# Sheet4.net
KiCad netlist of a schematic drawn in Altium Designer
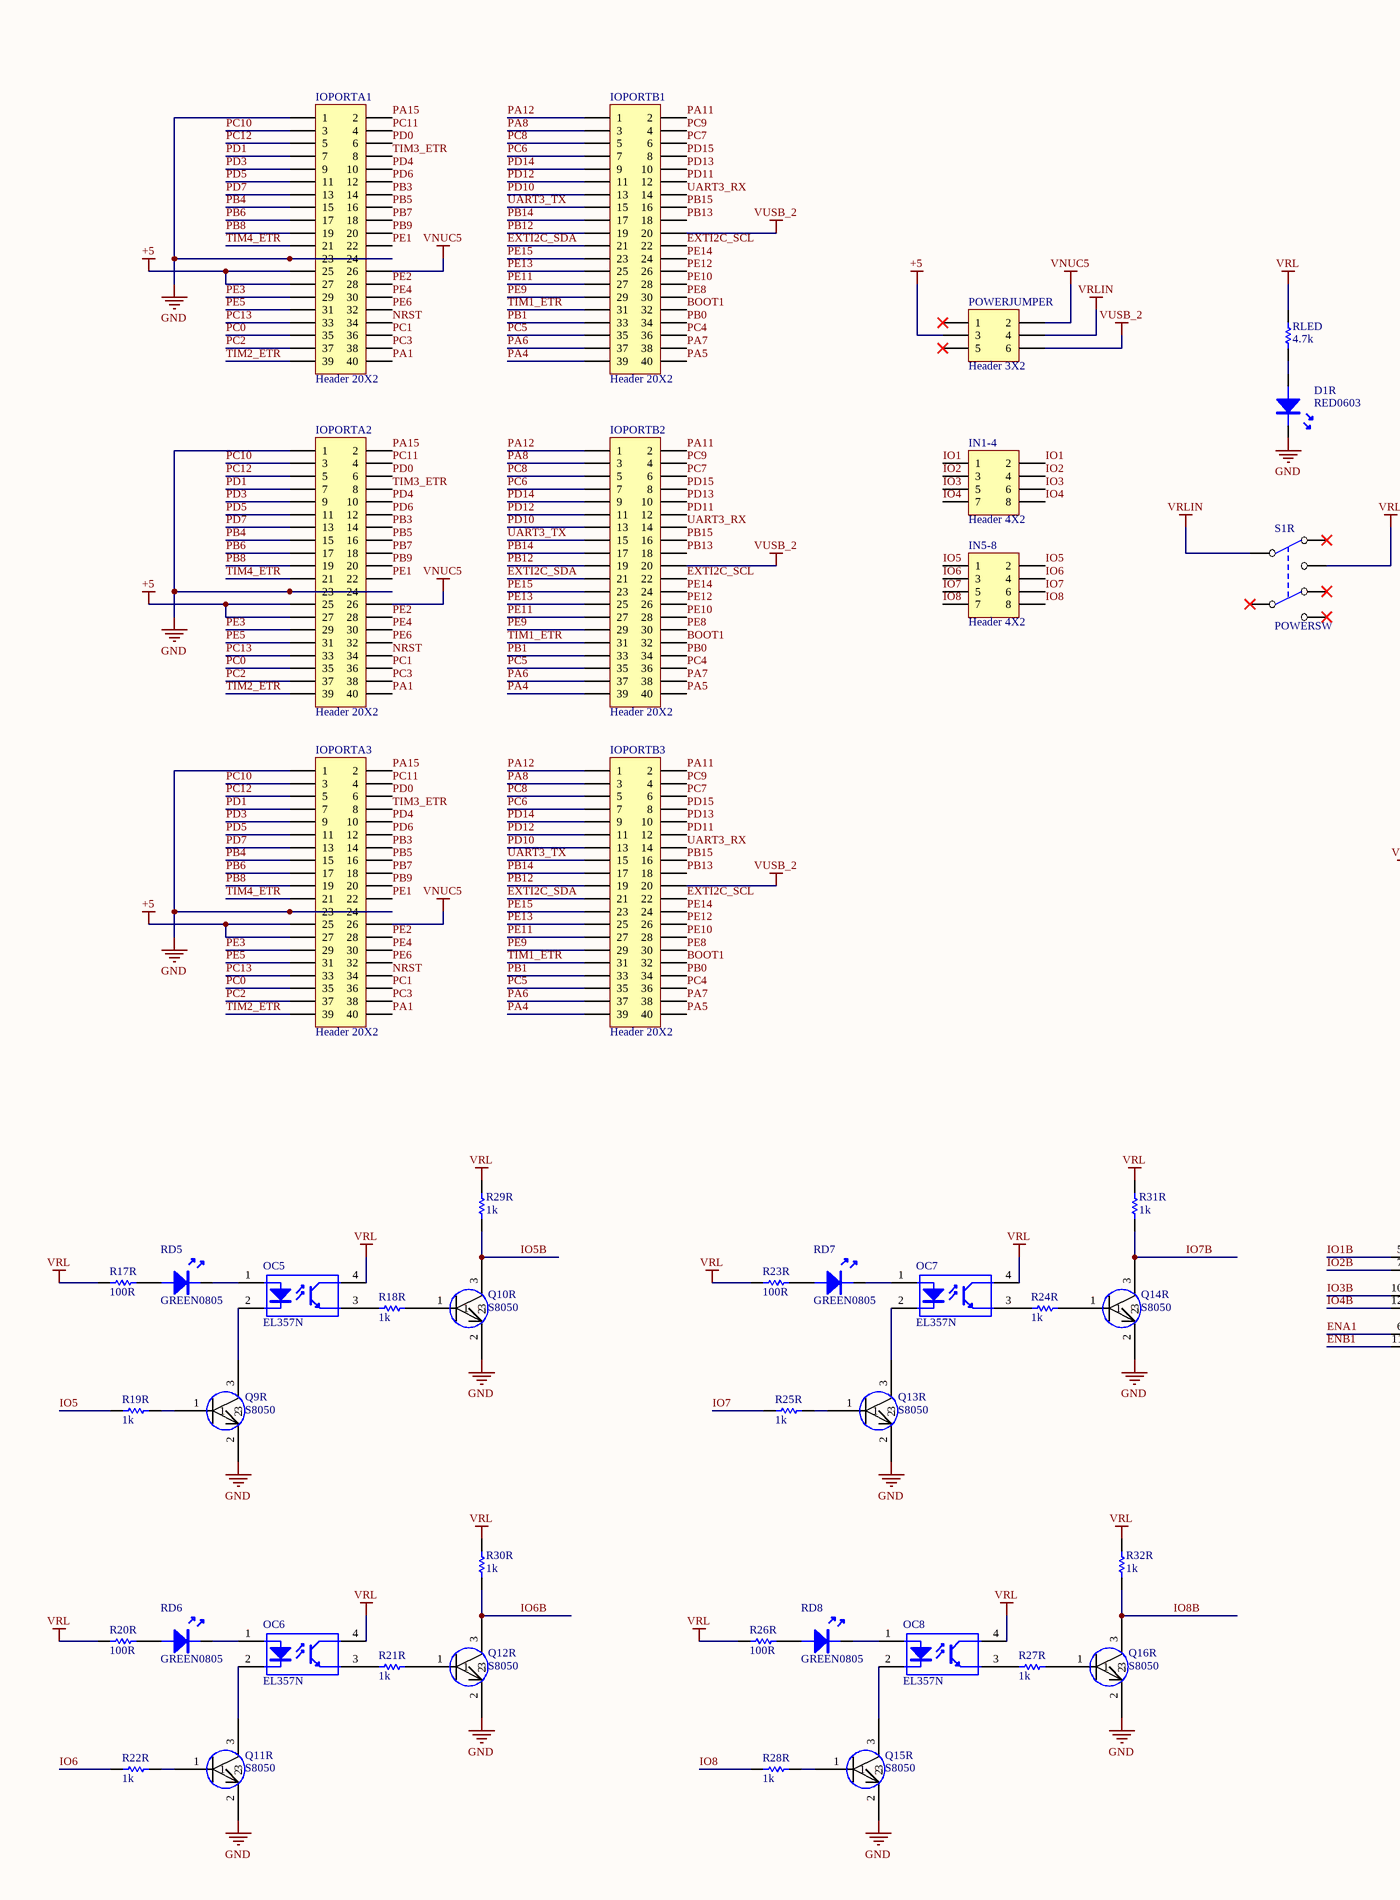
[diagram p0: Sheet4.SchDoc, left]
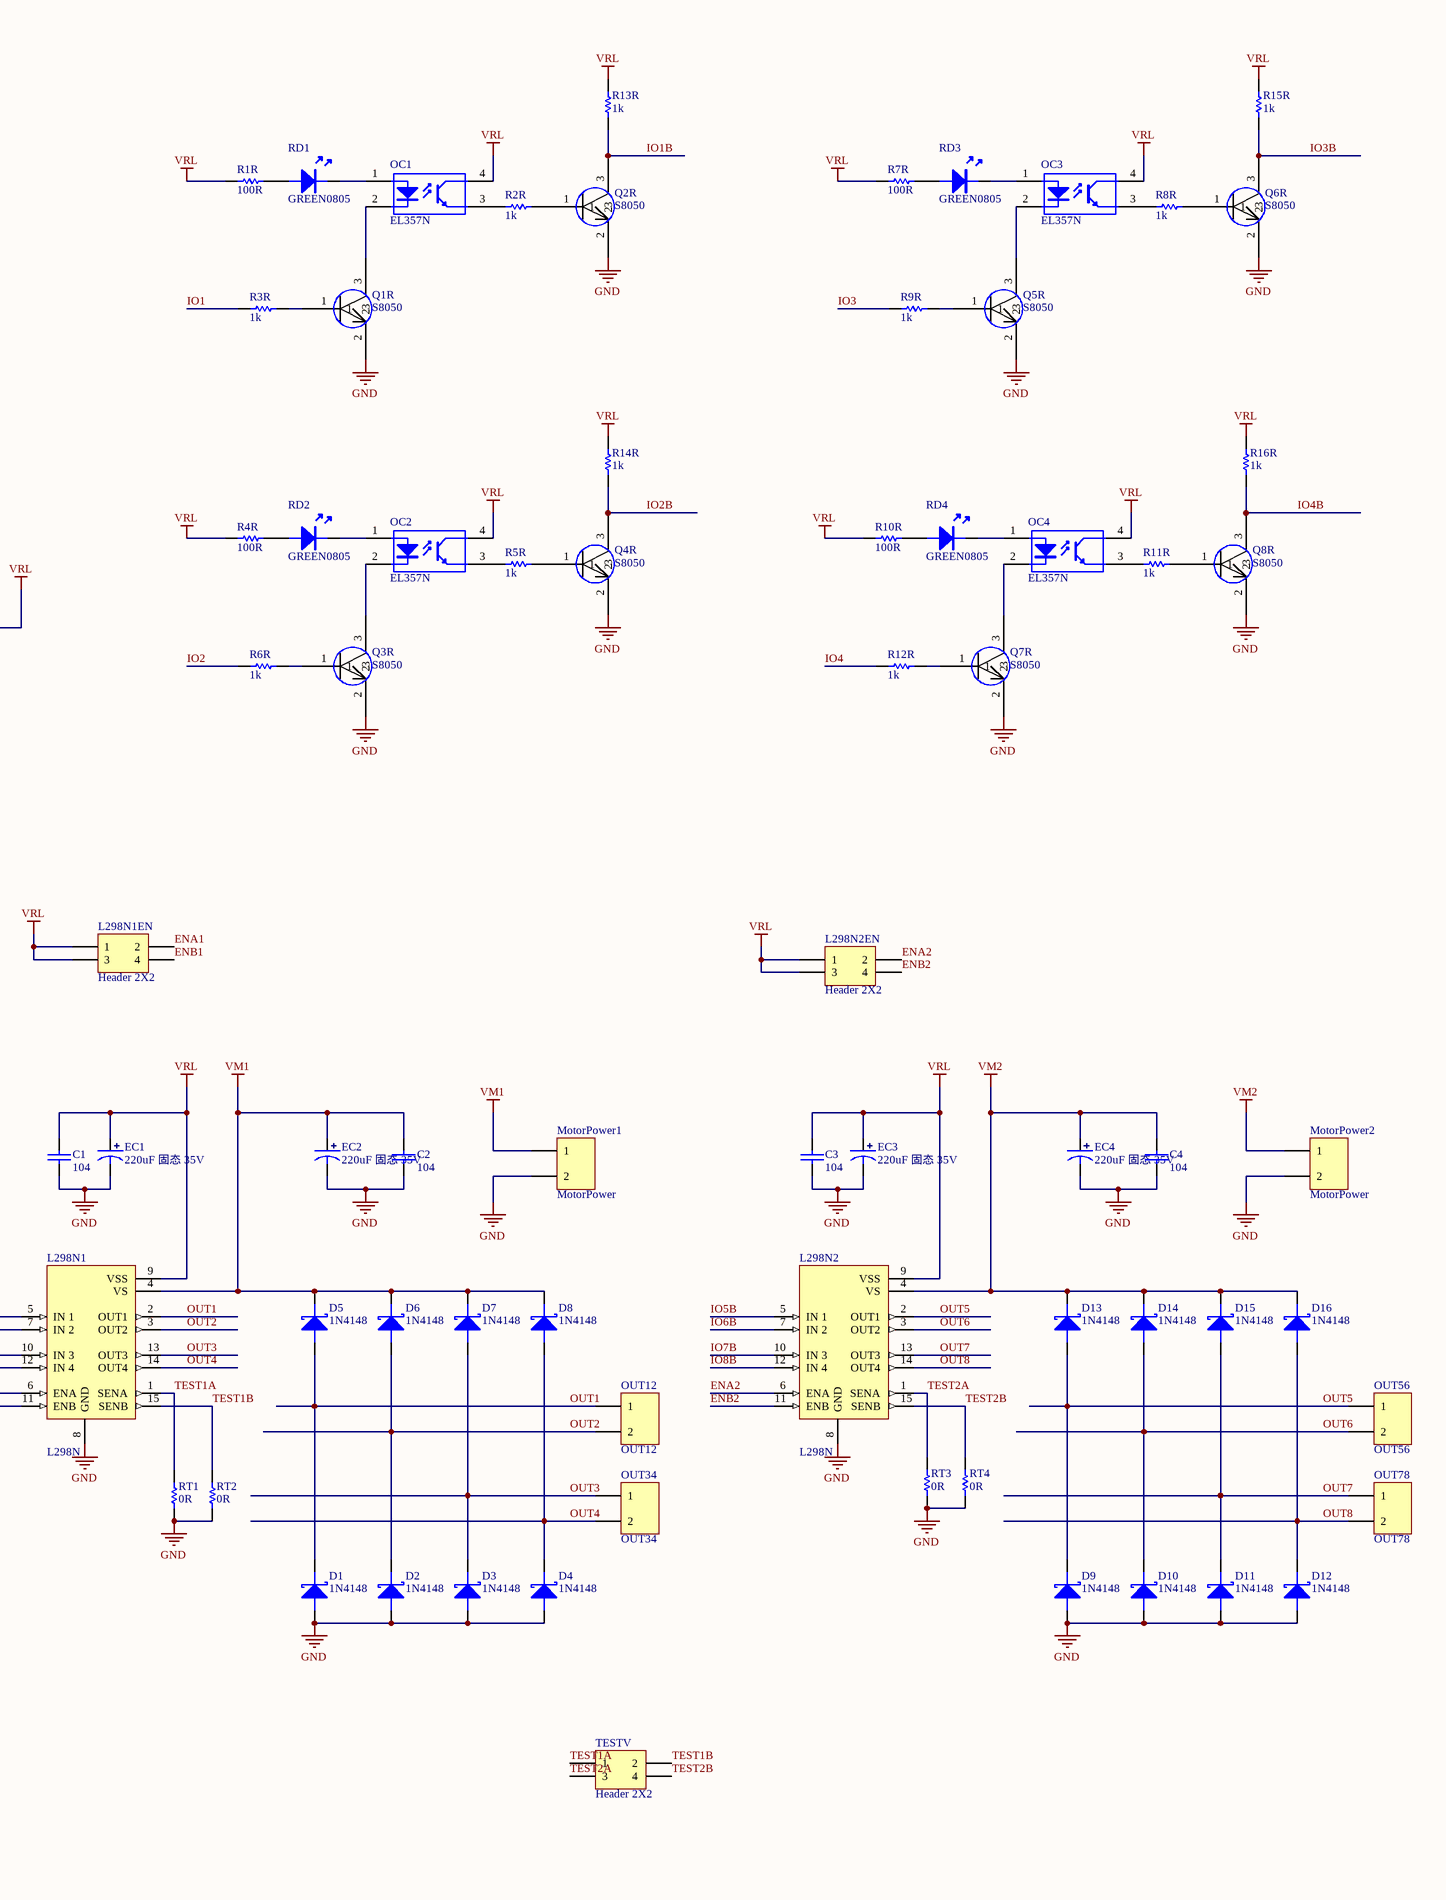
[diagram p1: Sheet4.SchDoc, right]

(export (version "E")
  (design (tool "Eeschema 10.0.6"))
  (components
    (comp (ref "C1")
      (value "104")
      (footprint "0805C")
      (description "无极性电容")
      (libsource (lib "Capacitance") (part "CAP"))
    )
    (comp (ref "C2")
      (value "104")
      (footprint "0805C")
      (description "无极性电容")
      (libsource (lib "Capacitance") (part "CAP"))
    )
    (comp (ref "C3")
      (value "104")
      (footprint "0805C")
      (description "无极性电容")
      (libsource (lib "Capacitance") (part "CAP"))
    )
    (comp (ref "C4")
      (value "104")
      (footprint "0805C")
      (description "无极性电容")
      (libsource (lib "Capacitance") (part "CAP"))
    )
    (comp (ref "D1")
      (value "1N4148")
      (footprint "SOD-323")
      (description "肖特基二极管")
      (libsource (lib "DIODE") (part "DIODE SCHOTTKY"))
    )
    (comp (ref "D1R") (value "RED0603") (footprint "LED-0603W") (libsource (lib "LED") (part "LED")))
    (comp (ref "D2")
      (value "1N4148")
      (footprint "SOD-323")
      (description "肖特基二极管")
      (libsource (lib "DIODE") (part "DIODE SCHOTTKY"))
    )
    (comp (ref "D3")
      (value "1N4148")
      (footprint "SOD-323")
      (description "肖特基二极管")
      (libsource (lib "DIODE") (part "DIODE SCHOTTKY"))
    )
    (comp (ref "D4")
      (value "1N4148")
      (footprint "SOD-323")
      (description "肖特基二极管")
      (libsource (lib "DIODE") (part "DIODE SCHOTTKY"))
    )
    (comp (ref "D5")
      (value "1N4148")
      (footprint "SOD-323")
      (description "肖特基二极管")
      (libsource (lib "DIODE") (part "DIODE SCHOTTKY"))
    )
    (comp (ref "D6")
      (value "1N4148")
      (footprint "SOD-323")
      (description "肖特基二极管")
      (libsource (lib "DIODE") (part "DIODE SCHOTTKY"))
    )
    (comp (ref "D7")
      (value "1N4148")
      (footprint "SOD-323")
      (description "肖特基二极管")
      (libsource (lib "DIODE") (part "DIODE SCHOTTKY"))
    )
    (comp (ref "D8")
      (value "1N4148")
      (footprint "SOD-323")
      (description "肖特基二极管")
      (libsource (lib "DIODE") (part "DIODE SCHOTTKY"))
    )
    (comp (ref "D9")
      (value "1N4148")
      (footprint "SOD-323")
      (description "肖特基二极管")
      (libsource (lib "DIODE") (part "DIODE SCHOTTKY"))
    )
    (comp (ref "D10")
      (value "1N4148")
      (footprint "SOD-323")
      (description "肖特基二极管")
      (libsource (lib "DIODE") (part "DIODE SCHOTTKY"))
    )
    (comp (ref "D11")
      (value "1N4148")
      (footprint "SOD-323")
      (description "肖特基二极管")
      (libsource (lib "DIODE") (part "DIODE SCHOTTKY"))
    )
    (comp (ref "D12")
      (value "1N4148")
      (footprint "SOD-323")
      (description "肖特基二极管")
      (libsource (lib "DIODE") (part "DIODE SCHOTTKY"))
    )
    (comp (ref "D13")
      (value "1N4148")
      (footprint "SOD-323")
      (description "肖特基二极管")
      (libsource (lib "DIODE") (part "DIODE SCHOTTKY"))
    )
    (comp (ref "D14")
      (value "1N4148")
      (footprint "SOD-323")
      (description "肖特基二极管")
      (libsource (lib "DIODE") (part "DIODE SCHOTTKY"))
    )
    (comp (ref "D15")
      (value "1N4148")
      (footprint "SOD-323")
      (description "肖特基二极管")
      (libsource (lib "DIODE") (part "DIODE SCHOTTKY"))
    )
    (comp (ref "D16")
      (value "1N4148")
      (footprint "SOD-323")
      (description "肖特基二极管")
      (libsource (lib "DIODE") (part "DIODE SCHOTTKY"))
    )
    (comp (ref "EC1")
      (value "220uF 固态 35V")
      (footprint "DIP-EC8X12")
      (description "直插电解电容")
      (libsource (lib "Capacitance") (part "DIP_ECAP"))
    )
    (comp (ref "EC2")
      (value "220uF 固态 35V")
      (footprint "DIP-EC8X12")
      (description "直插电解电容")
      (libsource (lib "Capacitance") (part "DIP_ECAP"))
    )
    (comp (ref "EC3")
      (value "220uF 固态 35V")
      (footprint "DIP-EC8X12")
      (description "直插电解电容")
      (libsource (lib "Capacitance") (part "DIP_ECAP"))
    )
    (comp (ref "EC4")
      (value "220uF 固态 35V")
      (footprint "DIP-EC8X12")
      (description "直插电解电容")
      (libsource (lib "Capacitance") (part "DIP_ECAP"))
    )
    (comp (ref "IN1-4")
      (value "Header 4X2")
      (footprint "HDR2X4")
      (description "Header, 4-Pin, Dual row")
      (fields (field (name "PUBLISHER") "Altium Limited"))
      (libsource (lib "Miscellaneous Connectors") (part "Header 4X2"))
    )
    (comp (ref "IN5-8")
      (value "Header 4X2")
      (footprint "HDR2X4")
      (description "Header, 4-Pin, Dual row")
      (fields (field (name "PUBLISHER") "Altium Limited"))
      (libsource (lib "Miscellaneous Connectors") (part "Header 4X2"))
    )
    (comp (ref "IOPORTA1")
      (value "Header 20X2")
      (footprint "HDR2X20")
      (description "Header, 20-Pin, Dual row")
      (fields (field (name "PUBLISHER") "Altium Limited"))
      (libsource (lib "Miscellaneous Connectors") (part "Header 20X2"))
    )
    (comp (ref "IOPORTA2")
      (value "Header 20X2")
      (footprint "HDR2X20")
      (description "Header, 20-Pin, Dual row")
      (fields (field (name "PUBLISHER") "Altium Limited"))
      (libsource (lib "Miscellaneous Connectors") (part "Header 20X2"))
    )
    (comp (ref "IOPORTA3")
      (value "Header 20X2")
      (footprint "HDR2X20")
      (description "Header, 20-Pin, Dual row")
      (fields (field (name "PUBLISHER") "Altium Limited"))
      (libsource (lib "Miscellaneous Connectors") (part "Header 20X2"))
    )
    (comp (ref "IOPORTB1")
      (value "Header 20X2")
      (footprint "HDR2X20")
      (description "Header, 20-Pin, Dual row")
      (fields (field (name "PUBLISHER") "Altium Limited"))
      (libsource (lib "Miscellaneous Connectors") (part "Header 20X2"))
    )
    (comp (ref "IOPORTB2")
      (value "Header 20X2")
      (footprint "HDR2X20")
      (description "Header, 20-Pin, Dual row")
      (fields (field (name "PUBLISHER") "Altium Limited"))
      (libsource (lib "Miscellaneous Connectors") (part "Header 20X2"))
    )
    (comp (ref "IOPORTB3")
      (value "Header 20X2")
      (footprint "HDR2X20")
      (description "Header, 20-Pin, Dual row")
      (fields (field (name "PUBLISHER") "Altium Limited"))
      (libsource (lib "Miscellaneous Connectors") (part "Header 20X2"))
    )
    (comp (ref "L298N1")
      (value "L298N")
      (footprint "L298N散热片")
      (description "MOTO DEVICE")
      (libsource (lib "未分类IC") (part "L298N"))
    )
    (comp (ref "L298N1EN")
      (value "Header 2X2")
      (footprint "HDR2X2")
      (description "Header, 2-Pin, Dual row")
      (fields (field (name "PUBLISHER") "Altium Limited"))
      (libsource (lib "Miscellaneous Connectors") (part "Header 2X2"))
    )
    (comp (ref "L298N2")
      (value "L298N")
      (footprint "L298N散热片")
      (description "MOTO DEVICE")
      (libsource (lib "未分类IC") (part "L298N"))
    )
    (comp (ref "L298N2EN")
      (value "Header 2X2")
      (footprint "HDR2X2")
      (description "Header, 2-Pin, Dual row")
      (fields (field (name "PUBLISHER") "Altium Limited"))
      (libsource (lib "Miscellaneous Connectors") (part "Header 2X2"))
    )
    (comp (ref "MotorPower1")
      (value "MotorPower")
      (footprint "KF301-2P")
      (libsource (lib "接线端子") (part "Connector-2P"))
    )
    (comp (ref "MotorPower2")
      (value "MotorPower")
      (footprint "KF301-2P")
      (libsource (lib "接线端子") (part "Connector-2P"))
    )
    (comp (ref "OC1")
      (value "EL357N")
      (footprint "SMD_EL357N")
      (description "线性光耦")
      (libsource (lib "光电隔离器") (part "EL357N"))
    )
    (comp (ref "OC2")
      (value "EL357N")
      (footprint "SMD_EL357N")
      (description "线性光耦")
      (libsource (lib "光电隔离器") (part "EL357N"))
    )
    (comp (ref "OC3")
      (value "EL357N")
      (footprint "SMD_EL357N")
      (description "线性光耦")
      (libsource (lib "光电隔离器") (part "EL357N"))
    )
    (comp (ref "OC4")
      (value "EL357N")
      (footprint "SMD_EL357N")
      (description "线性光耦")
      (libsource (lib "光电隔离器") (part "EL357N"))
    )
    (comp (ref "OC5")
      (value "EL357N")
      (footprint "SMD_EL357N")
      (description "线性光耦")
      (libsource (lib "光电隔离器") (part "EL357N"))
    )
    (comp (ref "OC6")
      (value "EL357N")
      (footprint "SMD_EL357N")
      (description "线性光耦")
      (libsource (lib "光电隔离器") (part "EL357N"))
    )
    (comp (ref "OC7")
      (value "EL357N")
      (footprint "SMD_EL357N")
      (description "线性光耦")
      (libsource (lib "光电隔离器") (part "EL357N"))
    )
    (comp (ref "OC8")
      (value "EL357N")
      (footprint "SMD_EL357N")
      (description "线性光耦")
      (libsource (lib "光电隔离器") (part "EL357N"))
    )
    (comp (ref "OUT12") (value "OUT12") (footprint "KF301-2P") (libsource (lib "接线端子") (part "Connector-2P")))
    (comp (ref "OUT34") (value "OUT34") (footprint "KF301-2P") (libsource (lib "接线端子") (part "Connector-2P")))
    (comp (ref "OUT56") (value "OUT56") (footprint "KF301-2P") (libsource (lib "接线端子") (part "Connector-2P")))
    (comp (ref "OUT78") (value "OUT78") (footprint "KF301-2P") (libsource (lib "接线端子") (part "Connector-2P")))
    (comp (ref "POWERJUMPER")
      (value "Header 3X2")
      (footprint "HDR2X3")
      (description "Header, 3-Pin, Dual row")
      (fields (field (name "PUBLISHER") "Altium Limited"))
      (libsource (lib "Miscellaneous Connectors") (part "Header 3X2"))
    )
    (comp (ref "Q1R") (value "S8050") (footprint "ics:SOT23") (libsource (lib "ics") (part "S9014")))
    (comp (ref "Q2R") (value "S8050") (footprint "ics:SOT23") (libsource (lib "ics") (part "S9014")))
    (comp (ref "Q3R") (value "S8050") (footprint "ics:SOT23") (libsource (lib "ics") (part "S9014")))
    (comp (ref "Q4R") (value "S8050") (footprint "ics:SOT23") (libsource (lib "ics") (part "S9014")))
    (comp (ref "Q5R") (value "S8050") (footprint "ics:SOT23") (libsource (lib "ics") (part "S9014")))
    (comp (ref "Q6R") (value "S8050") (footprint "ics:SOT23") (libsource (lib "ics") (part "S9014")))
    (comp (ref "Q7R") (value "S8050") (footprint "ics:SOT23") (libsource (lib "ics") (part "S9014")))
    (comp (ref "Q8R") (value "S8050") (footprint "ics:SOT23") (libsource (lib "ics") (part "S9014")))
    (comp (ref "Q9R") (value "S8050") (footprint "ics:SOT23") (libsource (lib "ics") (part "S9014")))
    (comp (ref "Q10R") (value "S8050") (footprint "ics:SOT23") (libsource (lib "ics") (part "S9014")))
    (comp (ref "Q11R") (value "S8050") (footprint "ics:SOT23") (libsource (lib "ics") (part "S9014")))
    (comp (ref "Q12R") (value "S8050") (footprint "ics:SOT23") (libsource (lib "ics") (part "S9014")))
    (comp (ref "Q13R") (value "S8050") (footprint "ics:SOT23") (libsource (lib "ics") (part "S9014")))
    (comp (ref "Q14R") (value "S8050") (footprint "ics:SOT23") (libsource (lib "ics") (part "S9014")))
    (comp (ref "Q15R") (value "S8050") (footprint "ics:SOT23") (libsource (lib "ics") (part "S9014")))
    (comp (ref "Q16R") (value "S8050") (footprint "ics:SOT23") (libsource (lib "ics") (part "S9014")))
    (comp (ref "R1R") (value "100R") (footprint "0603R") (libsource (lib "Resistance") (part "RES")))
    (comp (ref "R2R") (value "1k") (footprint "0603R") (libsource (lib "Resistance") (part "RES")))
    (comp (ref "R3R") (value "1k") (footprint "0603R") (libsource (lib "Resistance") (part "RES")))
    (comp (ref "R4R") (value "100R") (footprint "0603R") (libsource (lib "Resistance") (part "RES")))
    (comp (ref "R5R") (value "1k") (footprint "0603R") (libsource (lib "Resistance") (part "RES")))
    (comp (ref "R6R") (value "1k") (footprint "0603R") (libsource (lib "Resistance") (part "RES")))
    (comp (ref "R7R") (value "100R") (footprint "0603R") (libsource (lib "Resistance") (part "RES")))
    (comp (ref "R8R") (value "1k") (footprint "0603R") (libsource (lib "Resistance") (part "RES")))
    (comp (ref "R9R") (value "1k") (footprint "0603R") (libsource (lib "Resistance") (part "RES")))
    (comp (ref "R10R") (value "100R") (footprint "0603R") (libsource (lib "Resistance") (part "RES")))
    (comp (ref "R11R") (value "1k") (footprint "0603R") (libsource (lib "Resistance") (part "RES")))
    (comp (ref "R12R") (value "1k") (footprint "0603R") (libsource (lib "Resistance") (part "RES")))
    (comp (ref "R13R") (value "1k") (footprint "0603R") (libsource (lib "Resistance") (part "RES")))
    (comp (ref "R14R") (value "1k") (footprint "0603R") (libsource (lib "Resistance") (part "RES")))
    (comp (ref "R15R") (value "1k") (footprint "0603R") (libsource (lib "Resistance") (part "RES")))
    (comp (ref "R16R") (value "1k") (footprint "0603R") (libsource (lib "Resistance") (part "RES")))
    (comp (ref "R17R") (value "100R") (footprint "0603R") (libsource (lib "Resistance") (part "RES")))
    (comp (ref "R18R") (value "1k") (footprint "0603R") (libsource (lib "Resistance") (part "RES")))
    (comp (ref "R19R") (value "1k") (footprint "0603R") (libsource (lib "Resistance") (part "RES")))
    (comp (ref "R20R") (value "100R") (footprint "0603R") (libsource (lib "Resistance") (part "RES")))
    (comp (ref "R21R") (value "1k") (footprint "0603R") (libsource (lib "Resistance") (part "RES")))
    (comp (ref "R22R") (value "1k") (footprint "0603R") (libsource (lib "Resistance") (part "RES")))
    (comp (ref "R23R") (value "100R") (footprint "0603R") (libsource (lib "Resistance") (part "RES")))
    (comp (ref "R24R") (value "1k") (footprint "0603R") (libsource (lib "Resistance") (part "RES")))
    (comp (ref "R25R") (value "1k") (footprint "0603R") (libsource (lib "Resistance") (part "RES")))
    (comp (ref "R26R") (value "100R") (footprint "0603R") (libsource (lib "Resistance") (part "RES")))
    (comp (ref "R27R") (value "1k") (footprint "0603R") (libsource (lib "Resistance") (part "RES")))
    (comp (ref "R28R") (value "1k") (footprint "0603R") (libsource (lib "Resistance") (part "RES")))
    (comp (ref "R29R") (value "1k") (footprint "0603R") (libsource (lib "Resistance") (part "RES")))
    (comp (ref "R30R") (value "1k") (footprint "0603R") (libsource (lib "Resistance") (part "RES")))
    (comp (ref "R31R") (value "1k") (footprint "0603R") (libsource (lib "Resistance") (part "RES")))
    (comp (ref "R32R") (value "1k") (footprint "0603R") (libsource (lib "Resistance") (part "RES")))
    (comp (ref "RD1") (value "GREEN0805") (footprint "LED-0805G") (libsource (lib "LED") (part "LED")))
    (comp (ref "RD2") (value "GREEN0805") (footprint "LED-0805G") (libsource (lib "LED") (part "LED")))
    (comp (ref "RD3") (value "GREEN0805") (footprint "LED-0805G") (libsource (lib "LED") (part "LED")))
    (comp (ref "RD4") (value "GREEN0805") (footprint "LED-0805G") (libsource (lib "LED") (part "LED")))
    (comp (ref "RD5") (value "GREEN0805") (footprint "LED-0805G") (libsource (lib "LED") (part "LED")))
    (comp (ref "RD6") (value "GREEN0805") (footprint "LED-0805G") (libsource (lib "LED") (part "LED")))
    (comp (ref "RD7") (value "GREEN0805") (footprint "LED-0805G") (libsource (lib "LED") (part "LED")))
    (comp (ref "RD8") (value "GREEN0805") (footprint "LED-0805G") (libsource (lib "LED") (part "LED")))
    (comp (ref "RLED") (value "4.7k") (footprint "0603R") (libsource (lib "Resistance") (part "RES")))
    (comp (ref "RT1") (value "0R") (footprint "0603R") (libsource (lib "Resistance") (part "RES")))
    (comp (ref "RT2") (value "0R") (footprint "0603R") (libsource (lib "Resistance") (part "RES")))
    (comp (ref "RT3") (value "0R") (footprint "0603R") (libsource (lib "Resistance") (part "RES")))
    (comp (ref "RT4") (value "0R") (footprint "0603R") (libsource (lib "Resistance") (part "RES")))
    (comp (ref "S1R")
      (value "POWERSW")
      (footprint "KFT DIP-7X7")
      (libsource (lib "电源开关") (part "KFT DIP-7X7"))
    )
    (comp (ref "TESTV")
      (value "Header 2X2")
      (footprint "HDR2X2")
      (description "Header, 2-Pin, Dual row")
      (fields (field (name "PUBLISHER") "Altium Limited"))
      (libsource (lib "Miscellaneous Connectors") (part "Header 2X2"))
    )
  )
  (nets
    (net (code "1") (name "+5") (class "Default")
      (node (ref "IOPORTA1") (pin "25") (pinfunction "25_25") (pintype "passive"))
      (node (ref "IOPORTA1") (pin "27") (pinfunction "27_27") (pintype "passive"))
      (node (ref "IOPORTA2") (pin "25") (pinfunction "25_25") (pintype "passive"))
      (node (ref "IOPORTA2") (pin "27") (pinfunction "27_27") (pintype "passive"))
      (node (ref "IOPORTA3") (pin "25") (pinfunction "25_25") (pintype "passive"))
      (node (ref "IOPORTA3") (pin "27") (pinfunction "27_27") (pintype "passive"))
      (node (ref "POWERJUMPER") (pin "3") (pinfunction "3_3") (pintype "passive"))
    )
    (net (code "2") (name "/BOOT1") (class "Default")
      (node (ref "IOPORTB1") (pin "32") (pinfunction "32_32") (pintype "passive"))
      (node (ref "IOPORTB2") (pin "32") (pinfunction "32_32") (pintype "passive"))
      (node (ref "IOPORTB3") (pin "32") (pinfunction "32_32") (pintype "passive"))
    )
    (net (code "3") (name "/ENA1") (class "Default")
      (node (ref "L298N1") (pin "6") (pinfunction "ENA_6") (pintype "input"))
      (node (ref "L298N1EN") (pin "2") (pinfunction "2_2") (pintype "passive"))
    )
    (net (code "4") (name "/ENA2") (class "Default")
      (node (ref "L298N2") (pin "6") (pinfunction "ENA_6") (pintype "input"))
      (node (ref "L298N2EN") (pin "2") (pinfunction "2_2") (pintype "passive"))
    )
    (net (code "5") (name "/ENB1") (class "Default")
      (node (ref "L298N1") (pin "11") (pinfunction "ENB_11") (pintype "input"))
      (node (ref "L298N1EN") (pin "4") (pinfunction "4_4") (pintype "passive"))
    )
    (net (code "6") (name "/ENB2") (class "Default")
      (node (ref "L298N2") (pin "11") (pinfunction "ENB_11") (pintype "input"))
      (node (ref "L298N2EN") (pin "4") (pinfunction "4_4") (pintype "passive"))
    )
    (net (code "7") (name "/EXTI2C_SCL") (class "Default")
      (node (ref "IOPORTB1") (pin "22") (pinfunction "22_22") (pintype "passive"))
      (node (ref "IOPORTB2") (pin "22") (pinfunction "22_22") (pintype "passive"))
      (node (ref "IOPORTB3") (pin "22") (pinfunction "22_22") (pintype "passive"))
    )
    (net (code "8") (name "/EXTI2C_SDA") (class "Default")
      (node (ref "IOPORTB1") (pin "21") (pinfunction "21_21") (pintype "passive"))
      (node (ref "IOPORTB2") (pin "21") (pinfunction "21_21") (pintype "passive"))
      (node (ref "IOPORTB3") (pin "21") (pinfunction "21_21") (pintype "passive"))
    )
    (net (code "9") (name "/IO1") (class "Default")
      (node (ref "IN1-4") (pin "1") (pinfunction "1_1") (pintype "passive"))
      (node (ref "IN1-4") (pin "2") (pinfunction "2_2") (pintype "passive"))
      (node (ref "R3R") (pin "1") (pinfunction "1_1") (pintype "passive"))
    )
    (net (code "10") (name "/IO1B") (class "Default")
      (node (ref "L298N1") (pin "5") (pinfunction "IN_1_5") (pintype "input"))
      (node (ref "Q2R") (pin "3") (pinfunction "3_3") (pintype "passive"))
      (node (ref "R13R") (pin "1") (pinfunction "1_1") (pintype "passive"))
    )
    (net (code "11") (name "/IO2") (class "Default")
      (node (ref "IN1-4") (pin "3") (pinfunction "3_3") (pintype "passive"))
      (node (ref "IN1-4") (pin "4") (pinfunction "4_4") (pintype "passive"))
      (node (ref "R6R") (pin "1") (pinfunction "1_1") (pintype "passive"))
    )
    (net (code "12") (name "/IO2B") (class "Default")
      (node (ref "L298N1") (pin "7") (pinfunction "IN_2_7") (pintype "input"))
      (node (ref "Q4R") (pin "3") (pinfunction "3_3") (pintype "passive"))
      (node (ref "R14R") (pin "1") (pinfunction "1_1") (pintype "passive"))
    )
    (net (code "13") (name "/IO3") (class "Default")
      (node (ref "IN1-4") (pin "5") (pinfunction "5_5") (pintype "passive"))
      (node (ref "IN1-4") (pin "6") (pinfunction "6_6") (pintype "passive"))
      (node (ref "R9R") (pin "1") (pinfunction "1_1") (pintype "passive"))
    )
    (net (code "14") (name "/IO3B") (class "Default")
      (node (ref "L298N1") (pin "10") (pinfunction "IN_3_10") (pintype "input"))
      (node (ref "Q6R") (pin "3") (pinfunction "3_3") (pintype "passive"))
      (node (ref "R15R") (pin "1") (pinfunction "1_1") (pintype "passive"))
    )
    (net (code "15") (name "/IO4") (class "Default")
      (node (ref "IN1-4") (pin "7") (pinfunction "7_7") (pintype "passive"))
      (node (ref "IN1-4") (pin "8") (pinfunction "8_8") (pintype "passive"))
      (node (ref "R12R") (pin "1") (pinfunction "1_1") (pintype "passive"))
    )
    (net (code "16") (name "/IO4B") (class "Default")
      (node (ref "L298N1") (pin "12") (pinfunction "IN_4_12") (pintype "input"))
      (node (ref "Q8R") (pin "3") (pinfunction "3_3") (pintype "passive"))
      (node (ref "R16R") (pin "1") (pinfunction "1_1") (pintype "passive"))
    )
    (net (code "17") (name "/IO5") (class "Default")
      (node (ref "IN5-8") (pin "1") (pinfunction "1_1") (pintype "passive"))
      (node (ref "IN5-8") (pin "2") (pinfunction "2_2") (pintype "passive"))
      (node (ref "R19R") (pin "1") (pinfunction "1_1") (pintype "passive"))
    )
    (net (code "18") (name "/IO5B") (class "Default")
      (node (ref "L298N2") (pin "5") (pinfunction "IN_1_5") (pintype "input"))
      (node (ref "Q10R") (pin "3") (pinfunction "3_3") (pintype "passive"))
      (node (ref "R29R") (pin "1") (pinfunction "1_1") (pintype "passive"))
    )
    (net (code "19") (name "/IO6") (class "Default")
      (node (ref "IN5-8") (pin "3") (pinfunction "3_3") (pintype "passive"))
      (node (ref "IN5-8") (pin "4") (pinfunction "4_4") (pintype "passive"))
      (node (ref "R22R") (pin "1") (pinfunction "1_1") (pintype "passive"))
    )
    (net (code "20") (name "/IO6B") (class "Default")
      (node (ref "L298N2") (pin "7") (pinfunction "IN_2_7") (pintype "input"))
      (node (ref "Q12R") (pin "3") (pinfunction "3_3") (pintype "passive"))
      (node (ref "R30R") (pin "1") (pinfunction "1_1") (pintype "passive"))
    )
    (net (code "21") (name "/IO7") (class "Default")
      (node (ref "IN5-8") (pin "5") (pinfunction "5_5") (pintype "passive"))
      (node (ref "IN5-8") (pin "6") (pinfunction "6_6") (pintype "passive"))
      (node (ref "R25R") (pin "1") (pinfunction "1_1") (pintype "passive"))
    )
    (net (code "22") (name "/IO7B") (class "Default")
      (node (ref "L298N2") (pin "10") (pinfunction "IN_3_10") (pintype "input"))
      (node (ref "Q14R") (pin "3") (pinfunction "3_3") (pintype "passive"))
      (node (ref "R31R") (pin "1") (pinfunction "1_1") (pintype "passive"))
    )
    (net (code "23") (name "/IO8") (class "Default")
      (node (ref "IN5-8") (pin "7") (pinfunction "7_7") (pintype "passive"))
      (node (ref "IN5-8") (pin "8") (pinfunction "8_8") (pintype "passive"))
      (node (ref "R28R") (pin "1") (pinfunction "1_1") (pintype "passive"))
    )
    (net (code "24") (name "/IO8B") (class "Default")
      (node (ref "L298N2") (pin "12") (pinfunction "IN_4_12") (pintype "input"))
      (node (ref "Q16R") (pin "3") (pinfunction "3_3") (pintype "passive"))
      (node (ref "R32R") (pin "1") (pinfunction "1_1") (pintype "passive"))
    )
    (net (code "25") (name "/NRST") (class "Default")
      (node (ref "IOPORTA1") (pin "34") (pinfunction "34_34") (pintype "passive"))
      (node (ref "IOPORTA2") (pin "34") (pinfunction "34_34") (pintype "passive"))
      (node (ref "IOPORTA3") (pin "34") (pinfunction "34_34") (pintype "passive"))
    )
    (net (code "26") (name "/OUT1") (class "Default")
      (node (ref "D1") (pin "K") (pinfunction "K_K") (pintype "passive"))
      (node (ref "D5") (pin "A") (pinfunction "A_A") (pintype "passive"))
      (node (ref "L298N1") (pin "2") (pinfunction "OUT1_2") (pintype "output"))
      (node (ref "OUT12") (pin "1") (pinfunction "1_1") (pintype "passive"))
    )
    (net (code "27") (name "/OUT2") (class "Default")
      (node (ref "D2") (pin "K") (pinfunction "K_K") (pintype "passive"))
      (node (ref "D6") (pin "A") (pinfunction "A_A") (pintype "passive"))
      (node (ref "L298N1") (pin "3") (pinfunction "OUT2_3") (pintype "output"))
      (node (ref "OUT12") (pin "2") (pinfunction "2_2") (pintype "passive"))
    )
    (net (code "28") (name "/OUT3") (class "Default")
      (node (ref "D3") (pin "K") (pinfunction "K_K") (pintype "passive"))
      (node (ref "D7") (pin "A") (pinfunction "A_A") (pintype "passive"))
      (node (ref "L298N1") (pin "13") (pinfunction "OUT3_13") (pintype "output"))
      (node (ref "OUT34") (pin "1") (pinfunction "1_1") (pintype "passive"))
    )
    (net (code "29") (name "/OUT4") (class "Default")
      (node (ref "D4") (pin "K") (pinfunction "K_K") (pintype "passive"))
      (node (ref "D8") (pin "A") (pinfunction "A_A") (pintype "passive"))
      (node (ref "L298N1") (pin "14") (pinfunction "OUT4_14") (pintype "output"))
      (node (ref "OUT34") (pin "2") (pinfunction "2_2") (pintype "passive"))
    )
    (net (code "30") (name "/OUT5") (class "Default")
      (node (ref "D13") (pin "A") (pinfunction "A_A") (pintype "passive"))
      (node (ref "D9") (pin "K") (pinfunction "K_K") (pintype "passive"))
      (node (ref "L298N2") (pin "2") (pinfunction "OUT1_2") (pintype "output"))
      (node (ref "OUT56") (pin "1") (pinfunction "1_1") (pintype "passive"))
    )
    (net (code "31") (name "/OUT6") (class "Default")
      (node (ref "D10") (pin "K") (pinfunction "K_K") (pintype "passive"))
      (node (ref "D14") (pin "A") (pinfunction "A_A") (pintype "passive"))
      (node (ref "L298N2") (pin "3") (pinfunction "OUT2_3") (pintype "output"))
      (node (ref "OUT56") (pin "2") (pinfunction "2_2") (pintype "passive"))
    )
    (net (code "32") (name "/OUT7") (class "Default")
      (node (ref "D11") (pin "K") (pinfunction "K_K") (pintype "passive"))
      (node (ref "D15") (pin "A") (pinfunction "A_A") (pintype "passive"))
      (node (ref "L298N2") (pin "13") (pinfunction "OUT3_13") (pintype "output"))
      (node (ref "OUT78") (pin "1") (pinfunction "1_1") (pintype "passive"))
    )
    (net (code "33") (name "/OUT8") (class "Default")
      (node (ref "D12") (pin "K") (pinfunction "K_K") (pintype "passive"))
      (node (ref "D16") (pin "A") (pinfunction "A_A") (pintype "passive"))
      (node (ref "L298N2") (pin "14") (pinfunction "OUT4_14") (pintype "output"))
      (node (ref "OUT78") (pin "2") (pinfunction "2_2") (pintype "passive"))
    )
    (net (code "34") (name "/PA1") (class "Default")
      (node (ref "IOPORTA1") (pin "40") (pinfunction "40_40") (pintype "passive"))
      (node (ref "IOPORTA2") (pin "40") (pinfunction "40_40") (pintype "passive"))
      (node (ref "IOPORTA3") (pin "40") (pinfunction "40_40") (pintype "passive"))
    )
    (net (code "35") (name "/PA4") (class "Default")
      (node (ref "IOPORTB1") (pin "39") (pinfunction "39_39") (pintype "passive"))
      (node (ref "IOPORTB2") (pin "39") (pinfunction "39_39") (pintype "passive"))
      (node (ref "IOPORTB3") (pin "39") (pinfunction "39_39") (pintype "passive"))
    )
    (net (code "36") (name "/PA5") (class "Default")
      (node (ref "IOPORTB1") (pin "40") (pinfunction "40_40") (pintype "passive"))
      (node (ref "IOPORTB2") (pin "40") (pinfunction "40_40") (pintype "passive"))
      (node (ref "IOPORTB3") (pin "40") (pinfunction "40_40") (pintype "passive"))
    )
    (net (code "37") (name "/PA6") (class "Default")
      (node (ref "IOPORTB1") (pin "37") (pinfunction "37_37") (pintype "passive"))
      (node (ref "IOPORTB2") (pin "37") (pinfunction "37_37") (pintype "passive"))
      (node (ref "IOPORTB3") (pin "37") (pinfunction "37_37") (pintype "passive"))
    )
    (net (code "38") (name "/PA7") (class "Default")
      (node (ref "IOPORTB1") (pin "38") (pinfunction "38_38") (pintype "passive"))
      (node (ref "IOPORTB2") (pin "38") (pinfunction "38_38") (pintype "passive"))
      (node (ref "IOPORTB3") (pin "38") (pinfunction "38_38") (pintype "passive"))
    )
    (net (code "39") (name "/PA8") (class "Default")
      (node (ref "IOPORTB1") (pin "3") (pinfunction "3_3") (pintype "passive"))
      (node (ref "IOPORTB2") (pin "3") (pinfunction "3_3") (pintype "passive"))
      (node (ref "IOPORTB3") (pin "3") (pinfunction "3_3") (pintype "passive"))
    )
    (net (code "40") (name "/PA11") (class "Default")
      (node (ref "IOPORTB1") (pin "2") (pinfunction "2_2") (pintype "passive"))
      (node (ref "IOPORTB2") (pin "2") (pinfunction "2_2") (pintype "passive"))
      (node (ref "IOPORTB3") (pin "2") (pinfunction "2_2") (pintype "passive"))
    )
    (net (code "41") (name "/PA12") (class "Default")
      (node (ref "IOPORTB1") (pin "1") (pinfunction "1_1") (pintype "passive"))
      (node (ref "IOPORTB2") (pin "1") (pinfunction "1_1") (pintype "passive"))
      (node (ref "IOPORTB3") (pin "1") (pinfunction "1_1") (pintype "passive"))
    )
    (net (code "42") (name "/PA15") (class "Default")
      (node (ref "IOPORTA1") (pin "2") (pinfunction "2_2") (pintype "passive"))
      (node (ref "IOPORTA2") (pin "2") (pinfunction "2_2") (pintype "passive"))
      (node (ref "IOPORTA3") (pin "2") (pinfunction "2_2") (pintype "passive"))
    )
    (net (code "43") (name "/PB0") (class "Default")
      (node (ref "IOPORTB1") (pin "34") (pinfunction "34_34") (pintype "passive"))
      (node (ref "IOPORTB2") (pin "34") (pinfunction "34_34") (pintype "passive"))
      (node (ref "IOPORTB3") (pin "34") (pinfunction "34_34") (pintype "passive"))
    )
    (net (code "44") (name "/PB1") (class "Default")
      (node (ref "IOPORTB1") (pin "33") (pinfunction "33_33") (pintype "passive"))
      (node (ref "IOPORTB2") (pin "33") (pinfunction "33_33") (pintype "passive"))
      (node (ref "IOPORTB3") (pin "33") (pinfunction "33_33") (pintype "passive"))
    )
    (net (code "45") (name "/PB3") (class "Default")
      (node (ref "IOPORTA1") (pin "14") (pinfunction "14_14") (pintype "passive"))
      (node (ref "IOPORTA2") (pin "14") (pinfunction "14_14") (pintype "passive"))
      (node (ref "IOPORTA3") (pin "14") (pinfunction "14_14") (pintype "passive"))
    )
    (net (code "46") (name "/PB4") (class "Default")
      (node (ref "IOPORTA1") (pin "15") (pinfunction "15_15") (pintype "passive"))
      (node (ref "IOPORTA2") (pin "15") (pinfunction "15_15") (pintype "passive"))
      (node (ref "IOPORTA3") (pin "15") (pinfunction "15_15") (pintype "passive"))
    )
    (net (code "47") (name "/PB5") (class "Default")
      (node (ref "IOPORTA1") (pin "16") (pinfunction "16_16") (pintype "passive"))
      (node (ref "IOPORTA2") (pin "16") (pinfunction "16_16") (pintype "passive"))
      (node (ref "IOPORTA3") (pin "16") (pinfunction "16_16") (pintype "passive"))
    )
    (net (code "48") (name "/PB6") (class "Default")
      (node (ref "IOPORTA1") (pin "17") (pinfunction "17_17") (pintype "passive"))
      (node (ref "IOPORTA2") (pin "17") (pinfunction "17_17") (pintype "passive"))
      (node (ref "IOPORTA3") (pin "17") (pinfunction "17_17") (pintype "passive"))
    )
    (net (code "49") (name "/PB7") (class "Default")
      (node (ref "IOPORTA1") (pin "18") (pinfunction "18_18") (pintype "passive"))
      (node (ref "IOPORTA2") (pin "18") (pinfunction "18_18") (pintype "passive"))
      (node (ref "IOPORTA3") (pin "18") (pinfunction "18_18") (pintype "passive"))
    )
    (net (code "50") (name "/PB8") (class "Default")
      (node (ref "IOPORTA1") (pin "19") (pinfunction "19_19") (pintype "passive"))
      (node (ref "IOPORTA2") (pin "19") (pinfunction "19_19") (pintype "passive"))
      (node (ref "IOPORTA3") (pin "19") (pinfunction "19_19") (pintype "passive"))
    )
    (net (code "51") (name "/PB9") (class "Default")
      (node (ref "IOPORTA1") (pin "20") (pinfunction "20_20") (pintype "passive"))
      (node (ref "IOPORTA2") (pin "20") (pinfunction "20_20") (pintype "passive"))
      (node (ref "IOPORTA3") (pin "20") (pinfunction "20_20") (pintype "passive"))
    )
    (net (code "52") (name "/PB12") (class "Default")
      (node (ref "IOPORTB1") (pin "19") (pinfunction "19_19") (pintype "passive"))
      (node (ref "IOPORTB2") (pin "19") (pinfunction "19_19") (pintype "passive"))
      (node (ref "IOPORTB3") (pin "19") (pinfunction "19_19") (pintype "passive"))
    )
    (net (code "53") (name "/PB13") (class "Default")
      (node (ref "IOPORTB1") (pin "18") (pinfunction "18_18") (pintype "passive"))
      (node (ref "IOPORTB2") (pin "18") (pinfunction "18_18") (pintype "passive"))
      (node (ref "IOPORTB3") (pin "18") (pinfunction "18_18") (pintype "passive"))
    )
    (net (code "54") (name "/PB14") (class "Default")
      (node (ref "IOPORTB1") (pin "17") (pinfunction "17_17") (pintype "passive"))
      (node (ref "IOPORTB2") (pin "17") (pinfunction "17_17") (pintype "passive"))
      (node (ref "IOPORTB3") (pin "17") (pinfunction "17_17") (pintype "passive"))
    )
    (net (code "55") (name "/PB15") (class "Default")
      (node (ref "IOPORTB1") (pin "16") (pinfunction "16_16") (pintype "passive"))
      (node (ref "IOPORTB2") (pin "16") (pinfunction "16_16") (pintype "passive"))
      (node (ref "IOPORTB3") (pin "16") (pinfunction "16_16") (pintype "passive"))
    )
    (net (code "56") (name "/PC0") (class "Default")
      (node (ref "IOPORTA1") (pin "35") (pinfunction "35_35") (pintype "passive"))
      (node (ref "IOPORTA2") (pin "35") (pinfunction "35_35") (pintype "passive"))
      (node (ref "IOPORTA3") (pin "35") (pinfunction "35_35") (pintype "passive"))
    )
    (net (code "57") (name "/PC1") (class "Default")
      (node (ref "IOPORTA1") (pin "36") (pinfunction "36_36") (pintype "passive"))
      (node (ref "IOPORTA2") (pin "36") (pinfunction "36_36") (pintype "passive"))
      (node (ref "IOPORTA3") (pin "36") (pinfunction "36_36") (pintype "passive"))
    )
    (net (code "58") (name "/PC2") (class "Default")
      (node (ref "IOPORTA1") (pin "37") (pinfunction "37_37") (pintype "passive"))
      (node (ref "IOPORTA2") (pin "37") (pinfunction "37_37") (pintype "passive"))
      (node (ref "IOPORTA3") (pin "37") (pinfunction "37_37") (pintype "passive"))
    )
    (net (code "59") (name "/PC3") (class "Default")
      (node (ref "IOPORTA1") (pin "38") (pinfunction "38_38") (pintype "passive"))
      (node (ref "IOPORTA2") (pin "38") (pinfunction "38_38") (pintype "passive"))
      (node (ref "IOPORTA3") (pin "38") (pinfunction "38_38") (pintype "passive"))
    )
    (net (code "60") (name "/PC4") (class "Default")
      (node (ref "IOPORTB1") (pin "36") (pinfunction "36_36") (pintype "passive"))
      (node (ref "IOPORTB2") (pin "36") (pinfunction "36_36") (pintype "passive"))
      (node (ref "IOPORTB3") (pin "36") (pinfunction "36_36") (pintype "passive"))
    )
    (net (code "61") (name "/PC5") (class "Default")
      (node (ref "IOPORTB1") (pin "35") (pinfunction "35_35") (pintype "passive"))
      (node (ref "IOPORTB2") (pin "35") (pinfunction "35_35") (pintype "passive"))
      (node (ref "IOPORTB3") (pin "35") (pinfunction "35_35") (pintype "passive"))
    )
    (net (code "62") (name "/PC6") (class "Default")
      (node (ref "IOPORTB1") (pin "7") (pinfunction "7_7") (pintype "passive"))
      (node (ref "IOPORTB2") (pin "7") (pinfunction "7_7") (pintype "passive"))
      (node (ref "IOPORTB3") (pin "7") (pinfunction "7_7") (pintype "passive"))
    )
    (net (code "63") (name "/PC7") (class "Default")
      (node (ref "IOPORTB1") (pin "6") (pinfunction "6_6") (pintype "passive"))
      (node (ref "IOPORTB2") (pin "6") (pinfunction "6_6") (pintype "passive"))
      (node (ref "IOPORTB3") (pin "6") (pinfunction "6_6") (pintype "passive"))
    )
    (net (code "64") (name "/PC8") (class "Default")
      (node (ref "IOPORTB1") (pin "5") (pinfunction "5_5") (pintype "passive"))
      (node (ref "IOPORTB2") (pin "5") (pinfunction "5_5") (pintype "passive"))
      (node (ref "IOPORTB3") (pin "5") (pinfunction "5_5") (pintype "passive"))
    )
    (net (code "65") (name "/PC9") (class "Default")
      (node (ref "IOPORTB1") (pin "4") (pinfunction "4_4") (pintype "passive"))
      (node (ref "IOPORTB2") (pin "4") (pinfunction "4_4") (pintype "passive"))
      (node (ref "IOPORTB3") (pin "4") (pinfunction "4_4") (pintype "passive"))
    )
    (net (code "66") (name "/PC10") (class "Default")
      (node (ref "IOPORTA1") (pin "3") (pinfunction "3_3") (pintype "passive"))
      (node (ref "IOPORTA2") (pin "3") (pinfunction "3_3") (pintype "passive"))
      (node (ref "IOPORTA3") (pin "3") (pinfunction "3_3") (pintype "passive"))
    )
    (net (code "67") (name "/PC11") (class "Default")
      (node (ref "IOPORTA1") (pin "4") (pinfunction "4_4") (pintype "passive"))
      (node (ref "IOPORTA2") (pin "4") (pinfunction "4_4") (pintype "passive"))
      (node (ref "IOPORTA3") (pin "4") (pinfunction "4_4") (pintype "passive"))
    )
    (net (code "68") (name "/PC12") (class "Default")
      (node (ref "IOPORTA1") (pin "5") (pinfunction "5_5") (pintype "passive"))
      (node (ref "IOPORTA2") (pin "5") (pinfunction "5_5") (pintype "passive"))
      (node (ref "IOPORTA3") (pin "5") (pinfunction "5_5") (pintype "passive"))
    )
    (net (code "69") (name "/PC13") (class "Default")
      (node (ref "IOPORTA1") (pin "33") (pinfunction "33_33") (pintype "passive"))
      (node (ref "IOPORTA2") (pin "33") (pinfunction "33_33") (pintype "passive"))
      (node (ref "IOPORTA3") (pin "33") (pinfunction "33_33") (pintype "passive"))
    )
    (net (code "70") (name "/PD0") (class "Default")
      (node (ref "IOPORTA1") (pin "6") (pinfunction "6_6") (pintype "passive"))
      (node (ref "IOPORTA2") (pin "6") (pinfunction "6_6") (pintype "passive"))
      (node (ref "IOPORTA3") (pin "6") (pinfunction "6_6") (pintype "passive"))
    )
    (net (code "71") (name "/PD1") (class "Default")
      (node (ref "IOPORTA1") (pin "7") (pinfunction "7_7") (pintype "passive"))
      (node (ref "IOPORTA2") (pin "7") (pinfunction "7_7") (pintype "passive"))
      (node (ref "IOPORTA3") (pin "7") (pinfunction "7_7") (pintype "passive"))
    )
    (net (code "72") (name "/PD3") (class "Default")
      (node (ref "IOPORTA1") (pin "9") (pinfunction "9_9") (pintype "passive"))
      (node (ref "IOPORTA2") (pin "9") (pinfunction "9_9") (pintype "passive"))
      (node (ref "IOPORTA3") (pin "9") (pinfunction "9_9") (pintype "passive"))
    )
    (net (code "73") (name "/PD4") (class "Default")
      (node (ref "IOPORTA1") (pin "10") (pinfunction "10_10") (pintype "passive"))
      (node (ref "IOPORTA2") (pin "10") (pinfunction "10_10") (pintype "passive"))
      (node (ref "IOPORTA3") (pin "10") (pinfunction "10_10") (pintype "passive"))
    )
    (net (code "74") (name "/PD5") (class "Default")
      (node (ref "IOPORTA1") (pin "11") (pinfunction "11_11") (pintype "passive"))
      (node (ref "IOPORTA2") (pin "11") (pinfunction "11_11") (pintype "passive"))
      (node (ref "IOPORTA3") (pin "11") (pinfunction "11_11") (pintype "passive"))
    )
    (net (code "75") (name "/PD6") (class "Default")
      (node (ref "IOPORTA1") (pin "12") (pinfunction "12_12") (pintype "passive"))
      (node (ref "IOPORTA2") (pin "12") (pinfunction "12_12") (pintype "passive"))
      (node (ref "IOPORTA3") (pin "12") (pinfunction "12_12") (pintype "passive"))
    )
    (net (code "76") (name "/PD7") (class "Default")
      (node (ref "IOPORTA1") (pin "13") (pinfunction "13_13") (pintype "passive"))
      (node (ref "IOPORTA2") (pin "13") (pinfunction "13_13") (pintype "passive"))
      (node (ref "IOPORTA3") (pin "13") (pinfunction "13_13") (pintype "passive"))
    )
    (net (code "77") (name "/PD10") (class "Default")
      (node (ref "IOPORTB1") (pin "13") (pinfunction "13_13") (pintype "passive"))
      (node (ref "IOPORTB2") (pin "13") (pinfunction "13_13") (pintype "passive"))
      (node (ref "IOPORTB3") (pin "13") (pinfunction "13_13") (pintype "passive"))
    )
    (net (code "78") (name "/PD11") (class "Default")
      (node (ref "IOPORTB1") (pin "12") (pinfunction "12_12") (pintype "passive"))
      (node (ref "IOPORTB2") (pin "12") (pinfunction "12_12") (pintype "passive"))
      (node (ref "IOPORTB3") (pin "12") (pinfunction "12_12") (pintype "passive"))
    )
    (net (code "79") (name "/PD12") (class "Default")
      (node (ref "IOPORTB1") (pin "11") (pinfunction "11_11") (pintype "passive"))
      (node (ref "IOPORTB2") (pin "11") (pinfunction "11_11") (pintype "passive"))
      (node (ref "IOPORTB3") (pin "11") (pinfunction "11_11") (pintype "passive"))
    )
    (net (code "80") (name "/PD13") (class "Default")
      (node (ref "IOPORTB1") (pin "10") (pinfunction "10_10") (pintype "passive"))
      (node (ref "IOPORTB2") (pin "10") (pinfunction "10_10") (pintype "passive"))
      (node (ref "IOPORTB3") (pin "10") (pinfunction "10_10") (pintype "passive"))
    )
    (net (code "81") (name "/PD14") (class "Default")
      (node (ref "IOPORTB1") (pin "9") (pinfunction "9_9") (pintype "passive"))
      (node (ref "IOPORTB2") (pin "9") (pinfunction "9_9") (pintype "passive"))
      (node (ref "IOPORTB3") (pin "9") (pinfunction "9_9") (pintype "passive"))
    )
    (net (code "82") (name "/PD15") (class "Default")
      (node (ref "IOPORTB1") (pin "8") (pinfunction "8_8") (pintype "passive"))
      (node (ref "IOPORTB2") (pin "8") (pinfunction "8_8") (pintype "passive"))
      (node (ref "IOPORTB3") (pin "8") (pinfunction "8_8") (pintype "passive"))
    )
    (net (code "83") (name "/PE1") (class "Default")
      (node (ref "IOPORTA1") (pin "22") (pinfunction "22_22") (pintype "passive"))
      (node (ref "IOPORTA2") (pin "22") (pinfunction "22_22") (pintype "passive"))
      (node (ref "IOPORTA3") (pin "22") (pinfunction "22_22") (pintype "passive"))
    )
    (net (code "84") (name "/PE2") (class "Default")
      (node (ref "IOPORTA1") (pin "28") (pinfunction "28_28") (pintype "passive"))
      (node (ref "IOPORTA2") (pin "28") (pinfunction "28_28") (pintype "passive"))
      (node (ref "IOPORTA3") (pin "28") (pinfunction "28_28") (pintype "passive"))
    )
    (net (code "85") (name "/PE3") (class "Default")
      (node (ref "IOPORTA1") (pin "29") (pinfunction "29_29") (pintype "passive"))
      (node (ref "IOPORTA2") (pin "29") (pinfunction "29_29") (pintype "passive"))
      (node (ref "IOPORTA3") (pin "29") (pinfunction "29_29") (pintype "passive"))
    )
    (net (code "86") (name "/PE4") (class "Default")
      (node (ref "IOPORTA1") (pin "30") (pinfunction "30_30") (pintype "passive"))
      (node (ref "IOPORTA2") (pin "30") (pinfunction "30_30") (pintype "passive"))
      (node (ref "IOPORTA3") (pin "30") (pinfunction "30_30") (pintype "passive"))
    )
    (net (code "87") (name "/PE5") (class "Default")
      (node (ref "IOPORTA1") (pin "31") (pinfunction "31_31") (pintype "passive"))
      (node (ref "IOPORTA2") (pin "31") (pinfunction "31_31") (pintype "passive"))
      (node (ref "IOPORTA3") (pin "31") (pinfunction "31_31") (pintype "passive"))
    )
    (net (code "88") (name "/PE6") (class "Default")
      (node (ref "IOPORTA1") (pin "32") (pinfunction "32_32") (pintype "passive"))
      (node (ref "IOPORTA2") (pin "32") (pinfunction "32_32") (pintype "passive"))
      (node (ref "IOPORTA3") (pin "32") (pinfunction "32_32") (pintype "passive"))
    )
    (net (code "89") (name "/PE8") (class "Default")
      (node (ref "IOPORTB1") (pin "30") (pinfunction "30_30") (pintype "passive"))
      (node (ref "IOPORTB2") (pin "30") (pinfunction "30_30") (pintype "passive"))
      (node (ref "IOPORTB3") (pin "30") (pinfunction "30_30") (pintype "passive"))
    )
    (net (code "90") (name "/PE9") (class "Default")
      (node (ref "IOPORTB1") (pin "29") (pinfunction "29_29") (pintype "passive"))
      (node (ref "IOPORTB2") (pin "29") (pinfunction "29_29") (pintype "passive"))
      (node (ref "IOPORTB3") (pin "29") (pinfunction "29_29") (pintype "passive"))
    )
    (net (code "91") (name "/PE10") (class "Default")
      (node (ref "IOPORTB1") (pin "28") (pinfunction "28_28") (pintype "passive"))
      (node (ref "IOPORTB2") (pin "28") (pinfunction "28_28") (pintype "passive"))
      (node (ref "IOPORTB3") (pin "28") (pinfunction "28_28") (pintype "passive"))
    )
    (net (code "92") (name "/PE11") (class "Default")
      (node (ref "IOPORTB1") (pin "27") (pinfunction "27_27") (pintype "passive"))
      (node (ref "IOPORTB2") (pin "27") (pinfunction "27_27") (pintype "passive"))
      (node (ref "IOPORTB3") (pin "27") (pinfunction "27_27") (pintype "passive"))
    )
    (net (code "93") (name "/PE12") (class "Default")
      (node (ref "IOPORTB1") (pin "26") (pinfunction "26_26") (pintype "passive"))
      (node (ref "IOPORTB2") (pin "26") (pinfunction "26_26") (pintype "passive"))
      (node (ref "IOPORTB3") (pin "26") (pinfunction "26_26") (pintype "passive"))
    )
    (net (code "94") (name "/PE13") (class "Default")
      (node (ref "IOPORTB1") (pin "25") (pinfunction "25_25") (pintype "passive"))
      (node (ref "IOPORTB2") (pin "25") (pinfunction "25_25") (pintype "passive"))
      (node (ref "IOPORTB3") (pin "25") (pinfunction "25_25") (pintype "passive"))
    )
    (net (code "95") (name "/PE14") (class "Default")
      (node (ref "IOPORTB1") (pin "24") (pinfunction "24_24") (pintype "passive"))
      (node (ref "IOPORTB2") (pin "24") (pinfunction "24_24") (pintype "passive"))
      (node (ref "IOPORTB3") (pin "24") (pinfunction "24_24") (pintype "passive"))
    )
    (net (code "96") (name "/PE15") (class "Default")
      (node (ref "IOPORTB1") (pin "23") (pinfunction "23_23") (pintype "passive"))
      (node (ref "IOPORTB2") (pin "23") (pinfunction "23_23") (pintype "passive"))
      (node (ref "IOPORTB3") (pin "23") (pinfunction "23_23") (pintype "passive"))
    )
    (net (code "97") (name "/TEST1A") (class "Default")
      (node (ref "L298N1") (pin "1") (pinfunction "SENA_1") (pintype "output"))
      (node (ref "RT1") (pin "2") (pinfunction "2_2") (pintype "passive"))
      (node (ref "TESTV") (pin "1") (pinfunction "1_1") (pintype "passive"))
    )
    (net (code "98") (name "/TEST1B") (class "Default")
      (node (ref "L298N1") (pin "15") (pinfunction "SENB_15") (pintype "output"))
      (node (ref "RT2") (pin "2") (pinfunction "2_2") (pintype "passive"))
      (node (ref "TESTV") (pin "2") (pinfunction "2_2") (pintype "passive"))
    )
    (net (code "99") (name "/TEST2A") (class "Default")
      (node (ref "L298N2") (pin "1") (pinfunction "SENA_1") (pintype "output"))
      (node (ref "RT3") (pin "2") (pinfunction "2_2") (pintype "passive"))
      (node (ref "TESTV") (pin "3") (pinfunction "3_3") (pintype "passive"))
    )
    (net (code "100") (name "/TEST2B") (class "Default")
      (node (ref "L298N2") (pin "15") (pinfunction "SENB_15") (pintype "output"))
      (node (ref "RT4") (pin "2") (pinfunction "2_2") (pintype "passive"))
      (node (ref "TESTV") (pin "4") (pinfunction "4_4") (pintype "passive"))
    )
    (net (code "101") (name "/TIM1_ETR") (class "Default")
      (node (ref "IOPORTB1") (pin "31") (pinfunction "31_31") (pintype "passive"))
      (node (ref "IOPORTB2") (pin "31") (pinfunction "31_31") (pintype "passive"))
      (node (ref "IOPORTB3") (pin "31") (pinfunction "31_31") (pintype "passive"))
    )
    (net (code "102") (name "/TIM2_ETR") (class "Default")
      (node (ref "IOPORTA1") (pin "39") (pinfunction "39_39") (pintype "passive"))
      (node (ref "IOPORTA2") (pin "39") (pinfunction "39_39") (pintype "passive"))
      (node (ref "IOPORTA3") (pin "39") (pinfunction "39_39") (pintype "passive"))
    )
    (net (code "103") (name "/TIM3_ETR") (class "Default")
      (node (ref "IOPORTA1") (pin "8") (pinfunction "8_8") (pintype "passive"))
      (node (ref "IOPORTA2") (pin "8") (pinfunction "8_8") (pintype "passive"))
      (node (ref "IOPORTA3") (pin "8") (pinfunction "8_8") (pintype "passive"))
    )
    (net (code "104") (name "/TIM4_ETR") (class "Default")
      (node (ref "IOPORTA1") (pin "21") (pinfunction "21_21") (pintype "passive"))
      (node (ref "IOPORTA2") (pin "21") (pinfunction "21_21") (pintype "passive"))
      (node (ref "IOPORTA3") (pin "21") (pinfunction "21_21") (pintype "passive"))
    )
    (net (code "105") (name "/UART3_RX") (class "Default")
      (node (ref "IOPORTB1") (pin "14") (pinfunction "14_14") (pintype "passive"))
      (node (ref "IOPORTB2") (pin "14") (pinfunction "14_14") (pintype "passive"))
      (node (ref "IOPORTB3") (pin "14") (pinfunction "14_14") (pintype "passive"))
    )
    (net (code "106") (name "/UART3_TX") (class "Default")
      (node (ref "IOPORTB1") (pin "15") (pinfunction "15_15") (pintype "passive"))
      (node (ref "IOPORTB2") (pin "15") (pinfunction "15_15") (pintype "passive"))
      (node (ref "IOPORTB3") (pin "15") (pinfunction "15_15") (pintype "passive"))
    )
    (net (code "107") (name "GND") (class "Default")
      (node (ref "C1") (pin "1") (pinfunction "1_1") (pintype "passive"))
      (node (ref "C2") (pin "1") (pinfunction "1_1") (pintype "passive"))
      (node (ref "C3") (pin "1") (pinfunction "1_1") (pintype "passive"))
      (node (ref "C4") (pin "1") (pinfunction "1_1") (pintype "passive"))
      (node (ref "D1") (pin "A") (pinfunction "A_A") (pintype "passive"))
      (node (ref "D10") (pin "A") (pinfunction "A_A") (pintype "passive"))
      (node (ref "D11") (pin "A") (pinfunction "A_A") (pintype "passive"))
      (node (ref "D12") (pin "A") (pinfunction "A_A") (pintype "passive"))
      (node (ref "D1R") (pin "K") (pinfunction "K_K") (pintype "passive"))
      (node (ref "D2") (pin "A") (pinfunction "A_A") (pintype "passive"))
      (node (ref "D3") (pin "A") (pinfunction "A_A") (pintype "passive"))
      (node (ref "D4") (pin "A") (pinfunction "A_A") (pintype "passive"))
      (node (ref "D9") (pin "A") (pinfunction "A_A") (pintype "passive"))
      (node (ref "EC1") (pin "2") (pinfunction "2_2") (pintype "passive"))
      (node (ref "EC2") (pin "2") (pinfunction "2_2") (pintype "passive"))
      (node (ref "EC3") (pin "2") (pinfunction "2_2") (pintype "passive"))
      (node (ref "EC4") (pin "2") (pinfunction "2_2") (pintype "passive"))
      (node (ref "IOPORTA1") (pin "1") (pinfunction "1_1") (pintype "passive"))
      (node (ref "IOPORTA1") (pin "23") (pinfunction "23_23") (pintype "passive"))
      (node (ref "IOPORTA1") (pin "24") (pinfunction "24_24") (pintype "passive"))
      (node (ref "IOPORTA2") (pin "1") (pinfunction "1_1") (pintype "passive"))
      (node (ref "IOPORTA2") (pin "23") (pinfunction "23_23") (pintype "passive"))
      (node (ref "IOPORTA2") (pin "24") (pinfunction "24_24") (pintype "passive"))
      (node (ref "IOPORTA3") (pin "1") (pinfunction "1_1") (pintype "passive"))
      (node (ref "IOPORTA3") (pin "23") (pinfunction "23_23") (pintype "passive"))
      (node (ref "IOPORTA3") (pin "24") (pinfunction "24_24") (pintype "passive"))
      (node (ref "L298N1") (pin "8") (pinfunction "GND_8") (pintype "power_in"))
      (node (ref "L298N2") (pin "8") (pinfunction "GND_8") (pintype "power_in"))
      (node (ref "MotorPower1") (pin "2") (pinfunction "2_2") (pintype "passive"))
      (node (ref "MotorPower2") (pin "2") (pinfunction "2_2") (pintype "passive"))
      (node (ref "Q10R") (pin "2") (pinfunction "2_2") (pintype "passive"))
      (node (ref "Q11R") (pin "2") (pinfunction "2_2") (pintype "passive"))
      (node (ref "Q12R") (pin "2") (pinfunction "2_2") (pintype "passive"))
      (node (ref "Q13R") (pin "2") (pinfunction "2_2") (pintype "passive"))
      (node (ref "Q14R") (pin "2") (pinfunction "2_2") (pintype "passive"))
      (node (ref "Q15R") (pin "2") (pinfunction "2_2") (pintype "passive"))
      (node (ref "Q16R") (pin "2") (pinfunction "2_2") (pintype "passive"))
      (node (ref "Q1R") (pin "2") (pinfunction "2_2") (pintype "passive"))
      (node (ref "Q2R") (pin "2") (pinfunction "2_2") (pintype "passive"))
      (node (ref "Q3R") (pin "2") (pinfunction "2_2") (pintype "passive"))
      (node (ref "Q4R") (pin "2") (pinfunction "2_2") (pintype "passive"))
      (node (ref "Q5R") (pin "2") (pinfunction "2_2") (pintype "passive"))
      (node (ref "Q6R") (pin "2") (pinfunction "2_2") (pintype "passive"))
      (node (ref "Q7R") (pin "2") (pinfunction "2_2") (pintype "passive"))
      (node (ref "Q8R") (pin "2") (pinfunction "2_2") (pintype "passive"))
      (node (ref "Q9R") (pin "2") (pinfunction "2_2") (pintype "passive"))
      (node (ref "RT1") (pin "1") (pinfunction "1_1") (pintype "passive"))
      (node (ref "RT2") (pin "1") (pinfunction "1_1") (pintype "passive"))
      (node (ref "RT3") (pin "1") (pinfunction "1_1") (pintype "passive"))
      (node (ref "RT4") (pin "1") (pinfunction "1_1") (pintype "passive"))
    )
    (net (code "108") (name "Net-(D1R-PadA)") (class "Default")
      (node (ref "D1R") (pin "A") (pinfunction "A_A") (pintype "passive"))
      (node (ref "RLED") (pin "1") (pinfunction "1_1") (pintype "passive"))
    )
    (net (code "109") (name "Net-(OC1-A)") (class "Default")
      (node (ref "OC1") (pin "1") (pinfunction "A_1") (pintype "passive"))
      (node (ref "RD1") (pin "K") (pinfunction "K_K") (pintype "passive"))
    )
    (net (code "110") (name "Net-(OC1-E)") (class "Default")
      (node (ref "OC1") (pin "3") (pinfunction "E_3") (pintype "passive"))
      (node (ref "R2R") (pin "1") (pinfunction "1_1") (pintype "passive"))
    )
    (net (code "111") (name "Net-(OC1-K)") (class "Default")
      (node (ref "OC1") (pin "2") (pinfunction "K_2") (pintype "passive"))
      (node (ref "Q1R") (pin "3") (pinfunction "3_3") (pintype "passive"))
    )
    (net (code "112") (name "Net-(OC2-A)") (class "Default")
      (node (ref "OC2") (pin "1") (pinfunction "A_1") (pintype "passive"))
      (node (ref "RD2") (pin "K") (pinfunction "K_K") (pintype "passive"))
    )
    (net (code "113") (name "Net-(OC2-E)") (class "Default")
      (node (ref "OC2") (pin "3") (pinfunction "E_3") (pintype "passive"))
      (node (ref "R5R") (pin "1") (pinfunction "1_1") (pintype "passive"))
    )
    (net (code "114") (name "Net-(OC2-K)") (class "Default")
      (node (ref "OC2") (pin "2") (pinfunction "K_2") (pintype "passive"))
      (node (ref "Q3R") (pin "3") (pinfunction "3_3") (pintype "passive"))
    )
    (net (code "115") (name "Net-(OC3-A)") (class "Default")
      (node (ref "OC3") (pin "1") (pinfunction "A_1") (pintype "passive"))
      (node (ref "RD3") (pin "K") (pinfunction "K_K") (pintype "passive"))
    )
    (net (code "116") (name "Net-(OC3-E)") (class "Default")
      (node (ref "OC3") (pin "3") (pinfunction "E_3") (pintype "passive"))
      (node (ref "R8R") (pin "1") (pinfunction "1_1") (pintype "passive"))
    )
    (net (code "117") (name "Net-(OC3-K)") (class "Default")
      (node (ref "OC3") (pin "2") (pinfunction "K_2") (pintype "passive"))
      (node (ref "Q5R") (pin "3") (pinfunction "3_3") (pintype "passive"))
    )
    (net (code "118") (name "Net-(OC4-A)") (class "Default")
      (node (ref "OC4") (pin "1") (pinfunction "A_1") (pintype "passive"))
      (node (ref "RD4") (pin "K") (pinfunction "K_K") (pintype "passive"))
    )
    (net (code "119") (name "Net-(OC4-E)") (class "Default")
      (node (ref "OC4") (pin "3") (pinfunction "E_3") (pintype "passive"))
      (node (ref "R11R") (pin "1") (pinfunction "1_1") (pintype "passive"))
    )
    (net (code "120") (name "Net-(OC4-K)") (class "Default")
      (node (ref "OC4") (pin "2") (pinfunction "K_2") (pintype "passive"))
      (node (ref "Q7R") (pin "3") (pinfunction "3_3") (pintype "passive"))
    )
    (net (code "121") (name "Net-(OC5-A)") (class "Default")
      (node (ref "OC5") (pin "1") (pinfunction "A_1") (pintype "passive"))
      (node (ref "RD5") (pin "K") (pinfunction "K_K") (pintype "passive"))
    )
    (net (code "122") (name "Net-(OC5-E)") (class "Default")
      (node (ref "OC5") (pin "3") (pinfunction "E_3") (pintype "passive"))
      (node (ref "R18R") (pin "1") (pinfunction "1_1") (pintype "passive"))
    )
    (net (code "123") (name "Net-(OC5-K)") (class "Default")
      (node (ref "OC5") (pin "2") (pinfunction "K_2") (pintype "passive"))
      (node (ref "Q9R") (pin "3") (pinfunction "3_3") (pintype "passive"))
    )
    (net (code "124") (name "Net-(OC6-A)") (class "Default")
      (node (ref "OC6") (pin "1") (pinfunction "A_1") (pintype "passive"))
      (node (ref "RD6") (pin "K") (pinfunction "K_K") (pintype "passive"))
    )
    (net (code "125") (name "Net-(OC6-E)") (class "Default")
      (node (ref "OC6") (pin "3") (pinfunction "E_3") (pintype "passive"))
      (node (ref "R21R") (pin "1") (pinfunction "1_1") (pintype "passive"))
    )
    (net (code "126") (name "Net-(OC6-K)") (class "Default")
      (node (ref "OC6") (pin "2") (pinfunction "K_2") (pintype "passive"))
      (node (ref "Q11R") (pin "3") (pinfunction "3_3") (pintype "passive"))
    )
    (net (code "127") (name "Net-(OC7-A)") (class "Default")
      (node (ref "OC7") (pin "1") (pinfunction "A_1") (pintype "passive"))
      (node (ref "RD7") (pin "K") (pinfunction "K_K") (pintype "passive"))
    )
    (net (code "128") (name "Net-(OC7-E)") (class "Default")
      (node (ref "OC7") (pin "3") (pinfunction "E_3") (pintype "passive"))
      (node (ref "R24R") (pin "1") (pinfunction "1_1") (pintype "passive"))
    )
    (net (code "129") (name "Net-(OC7-K)") (class "Default")
      (node (ref "OC7") (pin "2") (pinfunction "K_2") (pintype "passive"))
      (node (ref "Q13R") (pin "3") (pinfunction "3_3") (pintype "passive"))
    )
    (net (code "130") (name "Net-(OC8-A)") (class "Default")
      (node (ref "OC8") (pin "1") (pinfunction "A_1") (pintype "passive"))
      (node (ref "RD8") (pin "K") (pinfunction "K_K") (pintype "passive"))
    )
    (net (code "131") (name "Net-(OC8-E)") (class "Default")
      (node (ref "OC8") (pin "3") (pinfunction "E_3") (pintype "passive"))
      (node (ref "R27R") (pin "1") (pinfunction "1_1") (pintype "passive"))
    )
    (net (code "132") (name "Net-(OC8-K)") (class "Default")
      (node (ref "OC8") (pin "2") (pinfunction "K_2") (pintype "passive"))
      (node (ref "Q15R") (pin "3") (pinfunction "3_3") (pintype "passive"))
    )
    (net (code "133") (name "Net-(Q1R-Pad1)") (class "Default")
      (node (ref "Q1R") (pin "1") (pinfunction "1_1") (pintype "passive"))
      (node (ref "R3R") (pin "2") (pinfunction "2_2") (pintype "passive"))
    )
    (net (code "134") (name "Net-(Q2R-Pad1)") (class "Default")
      (node (ref "Q2R") (pin "1") (pinfunction "1_1") (pintype "passive"))
      (node (ref "R2R") (pin "2") (pinfunction "2_2") (pintype "passive"))
    )
    (net (code "135") (name "Net-(Q3R-Pad1)") (class "Default")
      (node (ref "Q3R") (pin "1") (pinfunction "1_1") (pintype "passive"))
      (node (ref "R6R") (pin "2") (pinfunction "2_2") (pintype "passive"))
    )
    (net (code "136") (name "Net-(Q4R-Pad1)") (class "Default")
      (node (ref "Q4R") (pin "1") (pinfunction "1_1") (pintype "passive"))
      (node (ref "R5R") (pin "2") (pinfunction "2_2") (pintype "passive"))
    )
    (net (code "137") (name "Net-(Q5R-Pad1)") (class "Default")
      (node (ref "Q5R") (pin "1") (pinfunction "1_1") (pintype "passive"))
      (node (ref "R9R") (pin "2") (pinfunction "2_2") (pintype "passive"))
    )
    (net (code "138") (name "Net-(Q6R-Pad1)") (class "Default")
      (node (ref "Q6R") (pin "1") (pinfunction "1_1") (pintype "passive"))
      (node (ref "R8R") (pin "2") (pinfunction "2_2") (pintype "passive"))
    )
    (net (code "139") (name "Net-(Q7R-Pad1)") (class "Default")
      (node (ref "Q7R") (pin "1") (pinfunction "1_1") (pintype "passive"))
      (node (ref "R12R") (pin "2") (pinfunction "2_2") (pintype "passive"))
    )
    (net (code "140") (name "Net-(Q8R-Pad1)") (class "Default")
      (node (ref "Q8R") (pin "1") (pinfunction "1_1") (pintype "passive"))
      (node (ref "R11R") (pin "2") (pinfunction "2_2") (pintype "passive"))
    )
    (net (code "141") (name "Net-(Q9R-Pad1)") (class "Default")
      (node (ref "Q9R") (pin "1") (pinfunction "1_1") (pintype "passive"))
      (node (ref "R19R") (pin "2") (pinfunction "2_2") (pintype "passive"))
    )
    (net (code "142") (name "Net-(Q10R-Pad1)") (class "Default")
      (node (ref "Q10R") (pin "1") (pinfunction "1_1") (pintype "passive"))
      (node (ref "R18R") (pin "2") (pinfunction "2_2") (pintype "passive"))
    )
    (net (code "143") (name "Net-(Q11R-Pad1)") (class "Default")
      (node (ref "Q11R") (pin "1") (pinfunction "1_1") (pintype "passive"))
      (node (ref "R22R") (pin "2") (pinfunction "2_2") (pintype "passive"))
    )
    (net (code "144") (name "Net-(Q12R-Pad1)") (class "Default")
      (node (ref "Q12R") (pin "1") (pinfunction "1_1") (pintype "passive"))
      (node (ref "R21R") (pin "2") (pinfunction "2_2") (pintype "passive"))
    )
    (net (code "145") (name "Net-(Q13R-Pad1)") (class "Default")
      (node (ref "Q13R") (pin "1") (pinfunction "1_1") (pintype "passive"))
      (node (ref "R25R") (pin "2") (pinfunction "2_2") (pintype "passive"))
    )
    (net (code "146") (name "Net-(Q14R-Pad1)") (class "Default")
      (node (ref "Q14R") (pin "1") (pinfunction "1_1") (pintype "passive"))
      (node (ref "R24R") (pin "2") (pinfunction "2_2") (pintype "passive"))
    )
    (net (code "147") (name "Net-(Q15R-Pad1)") (class "Default")
      (node (ref "Q15R") (pin "1") (pinfunction "1_1") (pintype "passive"))
      (node (ref "R28R") (pin "2") (pinfunction "2_2") (pintype "passive"))
    )
    (net (code "148") (name "Net-(Q16R-Pad1)") (class "Default")
      (node (ref "Q16R") (pin "1") (pinfunction "1_1") (pintype "passive"))
      (node (ref "R27R") (pin "2") (pinfunction "2_2") (pintype "passive"))
    )
    (net (code "149") (name "Net-(R1R-Pad2)") (class "Default")
      (node (ref "R1R") (pin "2") (pinfunction "2_2") (pintype "passive"))
      (node (ref "RD1") (pin "A") (pinfunction "A_A") (pintype "passive"))
    )
    (net (code "150") (name "Net-(R4R-Pad2)") (class "Default")
      (node (ref "R4R") (pin "2") (pinfunction "2_2") (pintype "passive"))
      (node (ref "RD2") (pin "A") (pinfunction "A_A") (pintype "passive"))
    )
    (net (code "151") (name "Net-(R7R-Pad2)") (class "Default")
      (node (ref "R7R") (pin "2") (pinfunction "2_2") (pintype "passive"))
      (node (ref "RD3") (pin "A") (pinfunction "A_A") (pintype "passive"))
    )
    (net (code "152") (name "Net-(R10R-Pad2)") (class "Default")
      (node (ref "R10R") (pin "2") (pinfunction "2_2") (pintype "passive"))
      (node (ref "RD4") (pin "A") (pinfunction "A_A") (pintype "passive"))
    )
    (net (code "153") (name "Net-(R17R-Pad2)") (class "Default")
      (node (ref "R17R") (pin "2") (pinfunction "2_2") (pintype "passive"))
      (node (ref "RD5") (pin "A") (pinfunction "A_A") (pintype "passive"))
    )
    (net (code "154") (name "Net-(R20R-Pad2)") (class "Default")
      (node (ref "R20R") (pin "2") (pinfunction "2_2") (pintype "passive"))
      (node (ref "RD6") (pin "A") (pinfunction "A_A") (pintype "passive"))
    )
    (net (code "155") (name "Net-(R23R-Pad2)") (class "Default")
      (node (ref "R23R") (pin "2") (pinfunction "2_2") (pintype "passive"))
      (node (ref "RD7") (pin "A") (pinfunction "A_A") (pintype "passive"))
    )
    (net (code "156") (name "Net-(R26R-Pad2)") (class "Default")
      (node (ref "R26R") (pin "2") (pinfunction "2_2") (pintype "passive"))
      (node (ref "RD8") (pin "A") (pinfunction "A_A") (pintype "passive"))
    )
    (net (code "157") (name "VM1") (class "Default")
      (node (ref "C2") (pin "2") (pinfunction "2_2") (pintype "passive"))
      (node (ref "D5") (pin "K") (pinfunction "K_K") (pintype "passive"))
      (node (ref "D6") (pin "K") (pinfunction "K_K") (pintype "passive"))
      (node (ref "D7") (pin "K") (pinfunction "K_K") (pintype "passive"))
      (node (ref "D8") (pin "K") (pinfunction "K_K") (pintype "passive"))
      (node (ref "EC2") (pin "1") (pinfunction "1_1") (pintype "passive"))
      (node (ref "L298N1") (pin "4") (pinfunction "VS_4") (pintype "power_in"))
      (node (ref "MotorPower1") (pin "1") (pinfunction "1_1") (pintype "passive"))
    )
    (net (code "158") (name "VM2") (class "Default")
      (node (ref "C4") (pin "2") (pinfunction "2_2") (pintype "passive"))
      (node (ref "D13") (pin "K") (pinfunction "K_K") (pintype "passive"))
      (node (ref "D14") (pin "K") (pinfunction "K_K") (pintype "passive"))
      (node (ref "D15") (pin "K") (pinfunction "K_K") (pintype "passive"))
      (node (ref "D16") (pin "K") (pinfunction "K_K") (pintype "passive"))
      (node (ref "EC4") (pin "1") (pinfunction "1_1") (pintype "passive"))
      (node (ref "L298N2") (pin "4") (pinfunction "VS_4") (pintype "power_in"))
      (node (ref "MotorPower2") (pin "1") (pinfunction "1_1") (pintype "passive"))
    )
    (net (code "159") (name "VNUC5") (class "Default")
      (node (ref "IOPORTA1") (pin "26") (pinfunction "26_26") (pintype "passive"))
      (node (ref "IOPORTA2") (pin "26") (pinfunction "26_26") (pintype "passive"))
      (node (ref "IOPORTA3") (pin "26") (pinfunction "26_26") (pintype "passive"))
      (node (ref "POWERJUMPER") (pin "2") (pinfunction "2_2") (pintype "passive"))
    )
    (net (code "160") (name "VRL") (class "Default")
      (node (ref "C1") (pin "2") (pinfunction "2_2") (pintype "passive"))
      (node (ref "C3") (pin "2") (pinfunction "2_2") (pintype "passive"))
      (node (ref "EC1") (pin "1") (pinfunction "1_1") (pintype "passive"))
      (node (ref "EC3") (pin "1") (pinfunction "1_1") (pintype "passive"))
      (node (ref "L298N1") (pin "9") (pinfunction "VSS_9") (pintype "power_in"))
      (node (ref "L298N1EN") (pin "1") (pinfunction "1_1") (pintype "passive"))
      (node (ref "L298N1EN") (pin "3") (pinfunction "3_3") (pintype "passive"))
      (node (ref "L298N2") (pin "9") (pinfunction "VSS_9") (pintype "power_in"))
      (node (ref "L298N2EN") (pin "1") (pinfunction "1_1") (pintype "passive"))
      (node (ref "L298N2EN") (pin "3") (pinfunction "3_3") (pintype "passive"))
      (node (ref "OC1") (pin "4") (pinfunction "C_4") (pintype "passive"))
      (node (ref "OC2") (pin "4") (pinfunction "C_4") (pintype "passive"))
      (node (ref "OC3") (pin "4") (pinfunction "C_4") (pintype "passive"))
      (node (ref "OC4") (pin "4") (pinfunction "C_4") (pintype "passive"))
      (node (ref "OC5") (pin "4") (pinfunction "C_4") (pintype "passive"))
      (node (ref "OC6") (pin "4") (pinfunction "C_4") (pintype "passive"))
      (node (ref "OC7") (pin "4") (pinfunction "C_4") (pintype "passive"))
      (node (ref "OC8") (pin "4") (pinfunction "C_4") (pintype "passive"))
      (node (ref "R10R") (pin "1") (pinfunction "1_1") (pintype "passive"))
      (node (ref "R13R") (pin "2") (pinfunction "2_2") (pintype "passive"))
      (node (ref "R14R") (pin "2") (pinfunction "2_2") (pintype "passive"))
      (node (ref "R15R") (pin "2") (pinfunction "2_2") (pintype "passive"))
      (node (ref "R16R") (pin "2") (pinfunction "2_2") (pintype "passive"))
      (node (ref "R17R") (pin "1") (pinfunction "1_1") (pintype "passive"))
      (node (ref "R1R") (pin "1") (pinfunction "1_1") (pintype "passive"))
      (node (ref "R20R") (pin "1") (pinfunction "1_1") (pintype "passive"))
      (node (ref "R23R") (pin "1") (pinfunction "1_1") (pintype "passive"))
      (node (ref "R26R") (pin "1") (pinfunction "1_1") (pintype "passive"))
      (node (ref "R29R") (pin "2") (pinfunction "2_2") (pintype "passive"))
      (node (ref "R30R") (pin "2") (pinfunction "2_2") (pintype "passive"))
      (node (ref "R31R") (pin "2") (pinfunction "2_2") (pintype "passive"))
      (node (ref "R32R") (pin "2") (pinfunction "2_2") (pintype "passive"))
      (node (ref "R4R") (pin "1") (pinfunction "1_1") (pintype "passive"))
      (node (ref "R7R") (pin "1") (pinfunction "1_1") (pintype "passive"))
      (node (ref "RLED") (pin "2") (pinfunction "2_2") (pintype "passive"))
      (node (ref "S1R") (pin "1") (pinfunction "1_1") (pintype "passive"))
    )
    (net (code "161") (name "VRLIN") (class "Default")
      (node (ref "POWERJUMPER") (pin "4") (pinfunction "4_4") (pintype "passive"))
      (node (ref "S1R") (pin "2") (pinfunction "2_2") (pintype "passive"))
    )
    (net (code "162") (name "VUSB_2") (class "Default")
      (node (ref "IOPORTB1") (pin "20") (pinfunction "20_20") (pintype "passive"))
      (node (ref "IOPORTB2") (pin "20") (pinfunction "20_20") (pintype "passive"))
      (node (ref "IOPORTB3") (pin "20") (pinfunction "20_20") (pintype "passive"))
      (node (ref "POWERJUMPER") (pin "6") (pinfunction "6_6") (pintype "passive"))
    )
    (net (code "163") (name "unconnected-(POWERJUMPER-Pad1)") (class "Default")
      (node (ref "POWERJUMPER") (pin "1") (pinfunction "1_1") (pintype "passive+no_connect"))
    )
    (net (code "164") (name "unconnected-(POWERJUMPER-Pad5)") (class "Default")
      (node (ref "POWERJUMPER") (pin "5") (pinfunction "5_5") (pintype "passive+no_connect"))
    )
    (net (code "165") (name "unconnected-(S1R-Pad3)") (class "Default")
      (node (ref "S1R") (pin "3") (pinfunction "3_3") (pintype "passive+no_connect"))
    )
    (net (code "166") (name "unconnected-(S1R-Pad4)") (class "Default")
      (node (ref "S1R") (pin "4") (pinfunction "4_4") (pintype "passive+no_connect"))
    )
    (net (code "167") (name "unconnected-(S1R-Pad5)") (class "Default")
      (node (ref "S1R") (pin "5") (pinfunction "5_5") (pintype "passive+no_connect"))
    )
    (net (code "168") (name "unconnected-(S1R-Pad6)") (class "Default")
      (node (ref "S1R") (pin "6") (pinfunction "6_6") (pintype "passive+no_connect"))
    )
  )
)
